# Pi-Fan-Controller_2021-02-07-eda-export.net
KiCad netlist of a schematic drawn in EasyEDA
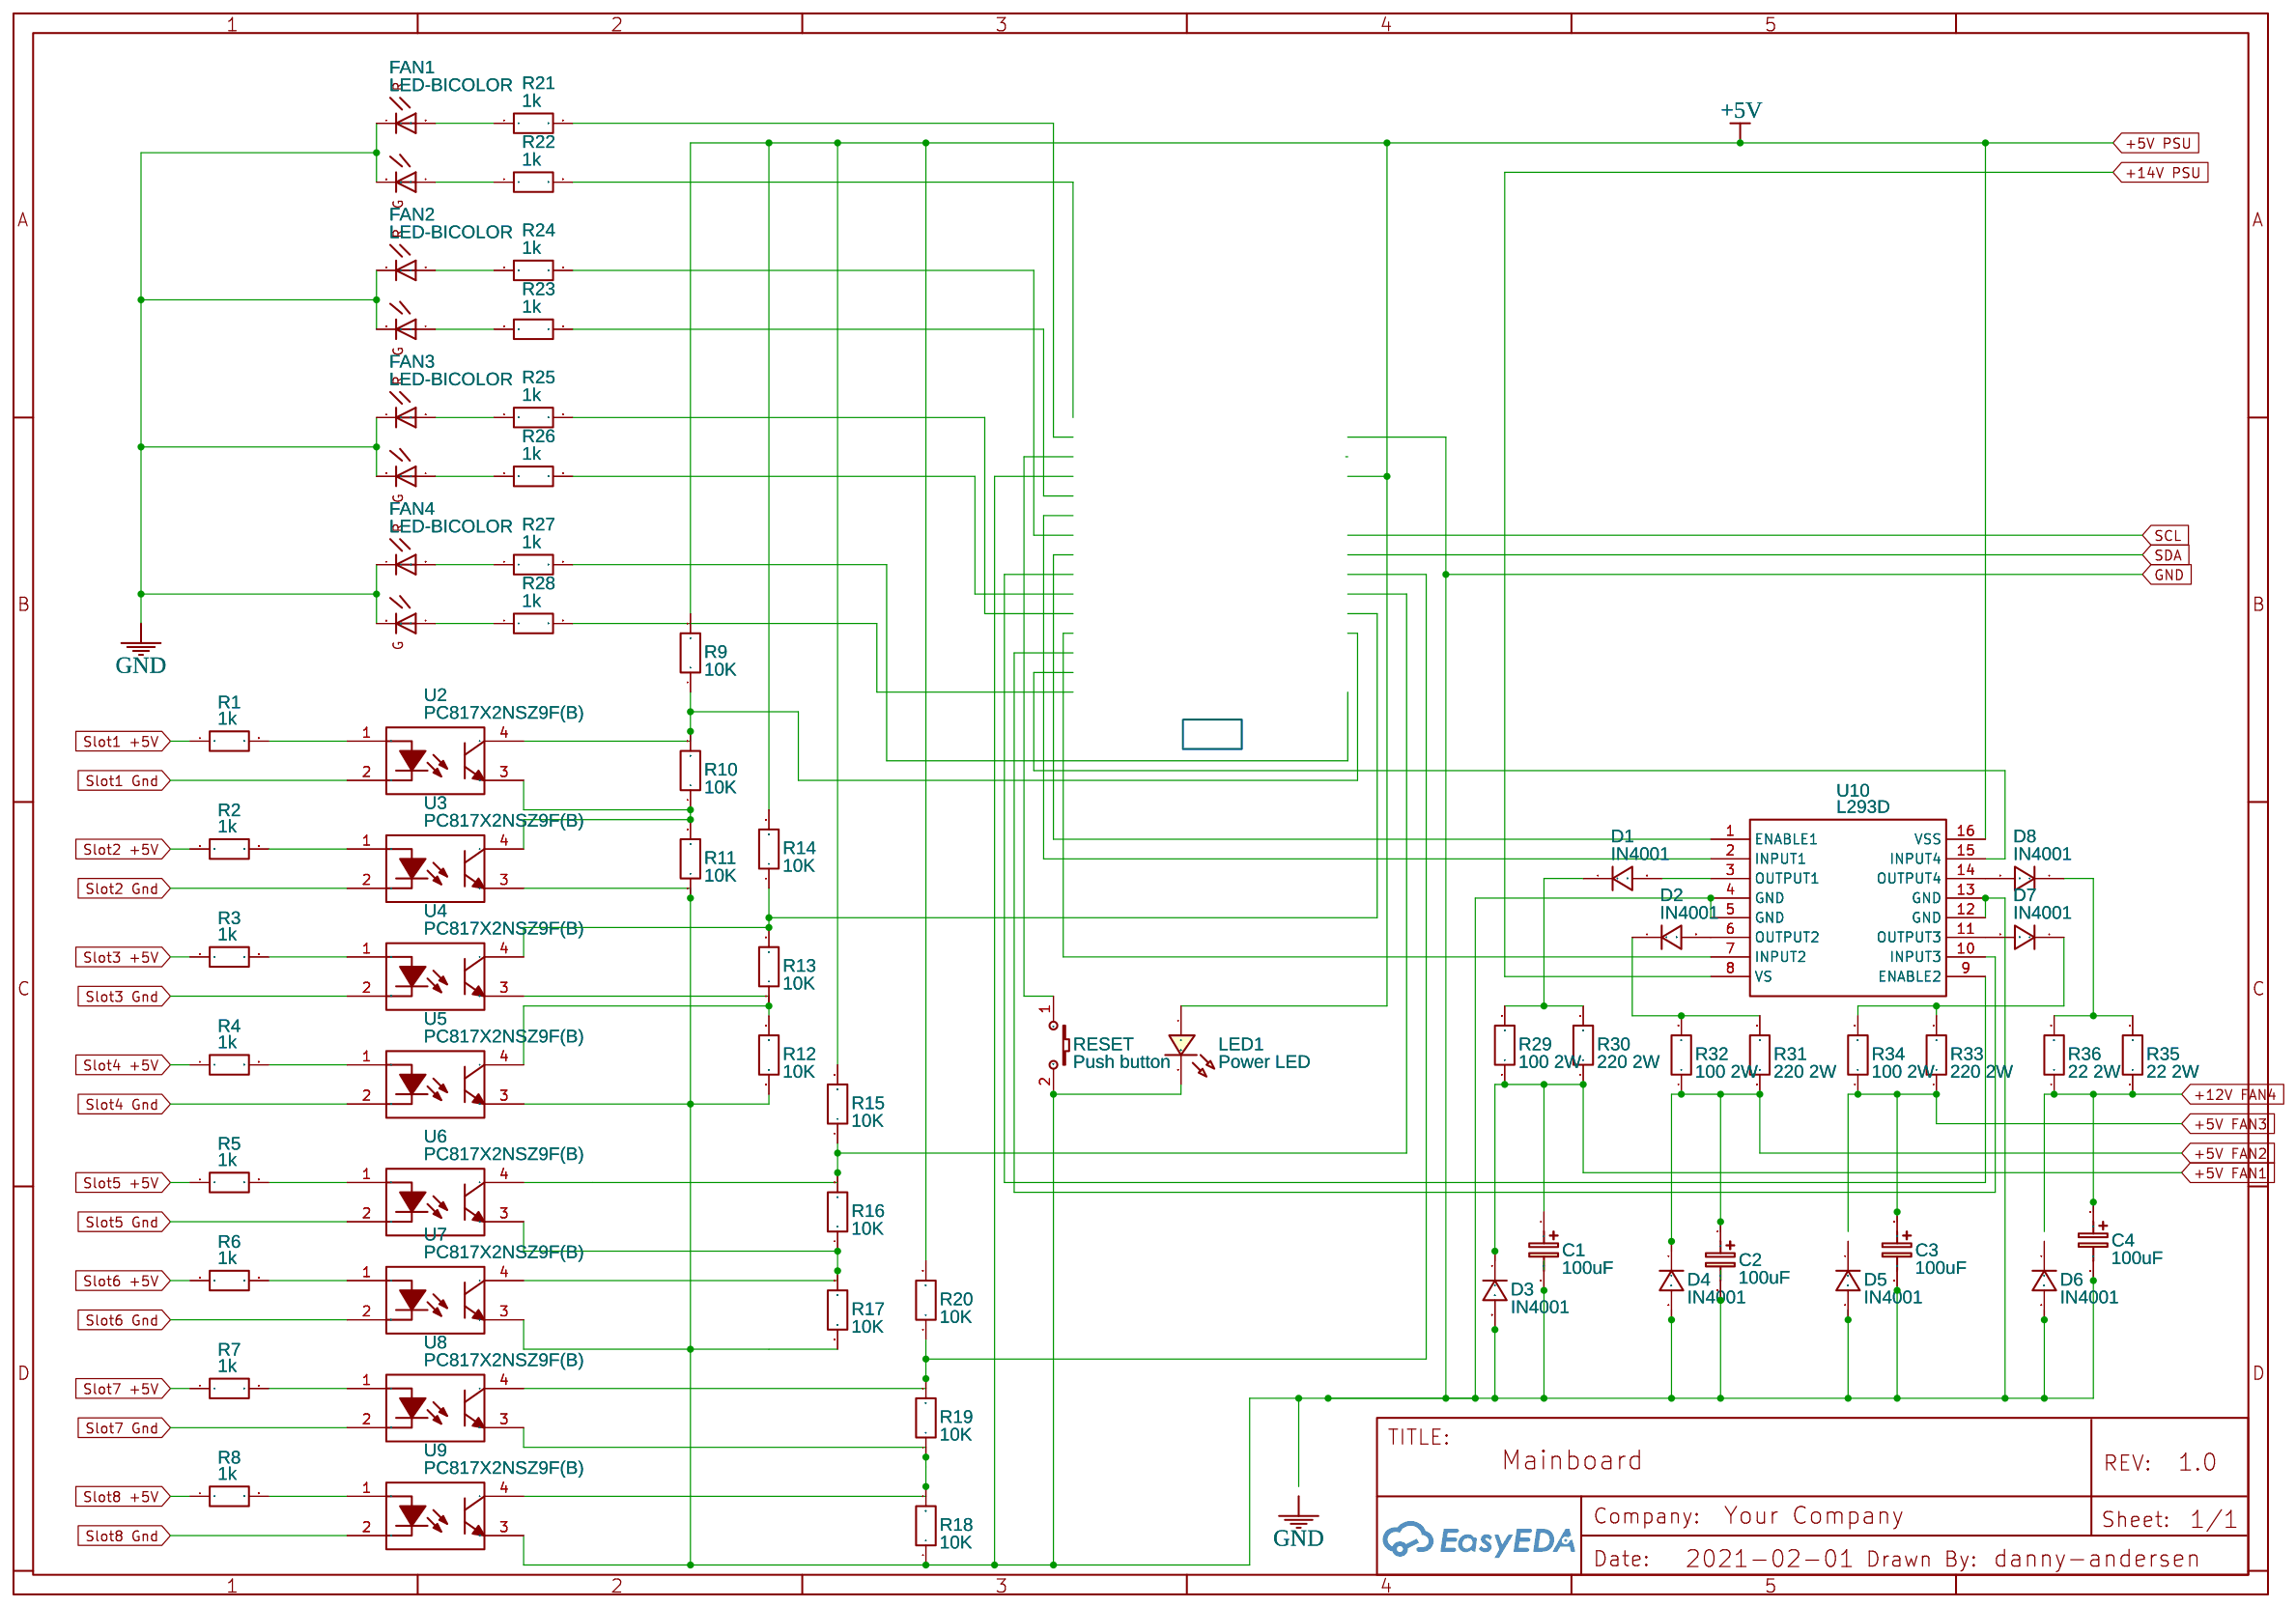
[diagram p0: schematic sheet]

(export (version "E")
  (design (tool "Eeschema 10.0.6"))
  (components
    (comp (ref "C1") (value "100uF") (libsource (lib "") (part "C_Tan_SMD_A_EU")))
    (comp (ref "C2") (value "100uF") (libsource (lib "") (part "C_Tan_SMD_A_EU")))
    (comp (ref "C3") (value "100uF") (libsource (lib "") (part "C_Tan_SMD_A_EU")))
    (comp (ref "C4") (value "100uF") (libsource (lib "") (part "C_Tan_SMD_A_EU_1")))
    (comp (ref "D1") (value "IN4001") (libsource (lib "") (part "IN4001_1")))
    (comp (ref "D2") (value "IN4001") (libsource (lib "") (part "IN4001_1")))
    (comp (ref "D3") (value "IN4001") (libsource (lib "") (part "IN4001")))
    (comp (ref "D4") (value "IN4001") (libsource (lib "") (part "IN4001")))
    (comp (ref "D5") (value "IN4001") (libsource (lib "") (part "IN4001")))
    (comp (ref "D6") (value "IN4001") (libsource (lib "") (part "IN4001")))
    (comp (ref "D7") (value "IN4001") (libsource (lib "") (part "IN4001_2")))
    (comp (ref "D8") (value "IN4001") (libsource (lib "") (part "IN4001_2")))
    (comp (ref "FAN1")
      (value "LED-BICOLOR")
      (fields (field (name "BOM_Manufacturer Part") "?"))
      (libsource (lib "") (part "Unknown_205_-750"))
    )
    (comp (ref "FAN2")
      (value "LED-BICOLOR")
      (fields (field (name "BOM_Manufacturer Part") "?"))
      (libsource (lib "") (part "Unknown_205_-675"))
    )
    (comp (ref "FAN3")
      (value "LED-BICOLOR")
      (fields (field (name "BOM_Manufacturer Part") "?"))
      (libsource (lib "") (part "Unknown_205_-600"))
    )
    (comp (ref "FAN4")
      (value "LED-BICOLOR")
      (fields (field (name "BOM_Manufacturer Part") "?"))
      (libsource (lib "") (part "Unknown_205_-525"))
    )
    (comp (ref "LED1")
      (value "Power LED")
      (fields
        (field (name "BOM_Manufacturer Part") "19-217/R6C-AL1M2VY/3T")
        (field (name "BOM_Supplier Part") "C72044")
      )
      (libsource (lib "") (part "LED-0603_R"))
    )
    (comp (ref "R1") (value "1k") (libsource (lib "") (part "R_0603_EU_1")))
    (comp (ref "R2") (value "1k") (libsource (lib "") (part "R_0603_EU_1")))
    (comp (ref "R3") (value "1k") (libsource (lib "") (part "R_0603_EU_1")))
    (comp (ref "R4") (value "1k") (libsource (lib "") (part "R_0603_EU_1")))
    (comp (ref "R5") (value "1k") (libsource (lib "") (part "R_0603_EU_1")))
    (comp (ref "R6") (value "1k") (libsource (lib "") (part "R_0603_EU_1")))
    (comp (ref "R7") (value "1k") (libsource (lib "") (part "R_0603_EU_1")))
    (comp (ref "R8") (value "1k") (libsource (lib "") (part "R_0603_EU_1")))
    (comp (ref "R9") (value "10K") (libsource (lib "") (part "R_0603_EU")))
    (comp (ref "R10") (value "10K") (libsource (lib "") (part "R_0603_EU")))
    (comp (ref "R11") (value "10K") (libsource (lib "") (part "R_0603_EU")))
    (comp (ref "R12") (value "10K") (libsource (lib "") (part "R_0603_EU")))
    (comp (ref "R13") (value "10K") (libsource (lib "") (part "R_0603_EU")))
    (comp (ref "R14") (value "10K") (libsource (lib "") (part "R_0603_EU")))
    (comp (ref "R15") (value "10K") (libsource (lib "") (part "R_0603_EU")))
    (comp (ref "R16") (value "10K") (libsource (lib "") (part "R_0603_EU")))
    (comp (ref "R17") (value "10K") (libsource (lib "") (part "R_0603_EU")))
    (comp (ref "R18") (value "10K") (libsource (lib "") (part "R_0603_EU")))
    (comp (ref "R19") (value "10K") (libsource (lib "") (part "R_0603_EU")))
    (comp (ref "R20") (value "10K") (libsource (lib "") (part "R_0603_EU")))
    (comp (ref "R21") (value "1k") (libsource (lib "") (part "R_0603_EU_1")))
    (comp (ref "R22") (value "1k") (libsource (lib "") (part "R_0603_EU_1")))
    (comp (ref "R23") (value "1k") (libsource (lib "") (part "R_0603_EU_1")))
    (comp (ref "R24") (value "1k") (libsource (lib "") (part "R_0603_EU_1")))
    (comp (ref "R25") (value "1k") (libsource (lib "") (part "R_0603_EU_1")))
    (comp (ref "R26") (value "1k") (libsource (lib "") (part "R_0603_EU_1")))
    (comp (ref "R27") (value "1k") (libsource (lib "") (part "R_0603_EU_1")))
    (comp (ref "R28") (value "1k") (libsource (lib "") (part "R_0603_EU_1")))
    (comp (ref "R29") (value "100 2W") (libsource (lib "") (part "R_0603_EU")))
    (comp (ref "R30") (value "220 2W") (libsource (lib "") (part "R_0603_EU")))
    (comp (ref "R31") (value "220 2W") (libsource (lib "") (part "R_0603_EU")))
    (comp (ref "R32") (value "100 2W") (libsource (lib "") (part "R_0603_EU")))
    (comp (ref "R33") (value "220 2W") (libsource (lib "") (part "R_0603_EU")))
    (comp (ref "R34") (value "100 2W") (libsource (lib "") (part "R_0603_EU")))
    (comp (ref "R35") (value "22 2W") (libsource (lib "") (part "R_0603_EU")))
    (comp (ref "R36") (value "22 2W") (libsource (lib "") (part "R_0603_EU")))
    (comp (ref "RESET")
      (value "Push button")
      (fields
        (field (name "BOM_Manufacturer Part") "K2-1107ST-A4SW-06")
        (field (name "BOM_Supplier Part") "C118141")
      )
      (libsource (lib "") (part "K2-3.6×6.1_SMD"))
    )
    (comp (ref "U2")
      (value "PC817X2NSZ9F(B)")
      (fields (field (name "BOM_Supplier Part") "C60965"))
      (libsource (lib "") (part "PC817X2NSZ9F(B)"))
    )
    (comp (ref "U3")
      (value "PC817X2NSZ9F(B)")
      (fields (field (name "BOM_Supplier Part") "C60965"))
      (libsource (lib "") (part "PC817X2NSZ9F(B)"))
    )
    (comp (ref "U4")
      (value "PC817X2NSZ9F(B)")
      (fields (field (name "BOM_Supplier Part") "C60965"))
      (libsource (lib "") (part "PC817X2NSZ9F(B)"))
    )
    (comp (ref "U5")
      (value "PC817X2NSZ9F(B)")
      (fields (field (name "BOM_Supplier Part") "C60965"))
      (libsource (lib "") (part "PC817X2NSZ9F(B)"))
    )
    (comp (ref "U6")
      (value "PC817X2NSZ9F(B)")
      (fields (field (name "BOM_Supplier Part") "C60965"))
      (libsource (lib "") (part "PC817X2NSZ9F(B)"))
    )
    (comp (ref "U7")
      (value "PC817X2NSZ9F(B)")
      (fields (field (name "BOM_Supplier Part") "C60965"))
      (libsource (lib "") (part "PC817X2NSZ9F(B)"))
    )
    (comp (ref "U8")
      (value "PC817X2NSZ9F(B)")
      (fields (field (name "BOM_Supplier Part") "C60965"))
      (libsource (lib "") (part "PC817X2NSZ9F(B)"))
    )
    (comp (ref "U9")
      (value "PC817X2NSZ9F(B)")
      (fields (field (name "BOM_Supplier Part") "C60965"))
      (libsource (lib "") (part "PC817X2NSZ9F(B)"))
    )
    (comp (ref "U10")
      (value "L293D")
      (fields (field (name "BOM_Supplier Part") "C12340"))
      (libsource (lib "") (part "L293D"))
    )
  )
  (nets
    (net (code "1") (name "+5V FAN1") (class "Default")
      (node (ref "C1") (pin "1") (pinfunction "1_1") (pintype "unspecified"))
      (node (ref "D3") (pin "1") (pinfunction "1_1") (pintype "unspecified"))
      (node (ref "R29") (pin "1") (pinfunction "1_1") (pintype "unspecified"))
      (node (ref "R30") (pin "1") (pinfunction "1_1") (pintype "unspecified"))
    )
    (net (code "2") (name "+5V FAN2") (class "Default")
      (node (ref "C2") (pin "1") (pinfunction "1_1") (pintype "unspecified"))
      (node (ref "D4") (pin "1") (pinfunction "1_1") (pintype "unspecified"))
      (node (ref "R31") (pin "1") (pinfunction "1_1") (pintype "unspecified"))
      (node (ref "R32") (pin "1") (pinfunction "1_1") (pintype "unspecified"))
    )
    (net (code "3") (name "+5V FAN3") (class "Default")
      (node (ref "C3") (pin "1") (pinfunction "1_1") (pintype "unspecified"))
      (node (ref "R33") (pin "1") (pinfunction "1_1") (pintype "unspecified"))
      (node (ref "R34") (pin "1") (pinfunction "1_1") (pintype "unspecified"))
    )
    (net (code "4") (name "+5V PSU") (class "Default")
      (node (ref "LED1") (pin "1") (pinfunction "1_1") (pintype "unspecified"))
      (node (ref "R14") (pin "2") (pinfunction "2_2") (pintype "unspecified"))
      (node (ref "R15") (pin "2") (pinfunction "2_2") (pintype "unspecified"))
      (node (ref "R20") (pin "2") (pinfunction "2_2") (pintype "unspecified"))
      (node (ref "R9") (pin "2") (pinfunction "2_2") (pintype "unspecified"))
      (node (ref "U10") (pin "16") (pinfunction "VSS_16") (pintype "unspecified"))
    )
    (net (code "5") (name "+12V FAN4") (class "Default")
      (node (ref "C4") (pin "1") (pinfunction "1_1") (pintype "unspecified"))
      (node (ref "R35") (pin "1") (pinfunction "1_1") (pintype "unspecified"))
      (node (ref "R36") (pin "1") (pinfunction "1_1") (pintype "unspecified"))
    )
    (net (code "6") (name "+14V PSU") (class "Default")
      (node (ref "U10") (pin "8") (pinfunction "VS_8") (pintype "unspecified"))
    )
    (net (code "7") (name "GND") (class "Default")
      (node (ref "C1") (pin "2") (pinfunction "2_2") (pintype "unspecified"))
      (node (ref "C2") (pin "2") (pinfunction "2_2") (pintype "unspecified"))
      (node (ref "C3") (pin "2") (pinfunction "2_2") (pintype "unspecified"))
      (node (ref "C4") (pin "2") (pinfunction "2_2") (pintype "unspecified"))
      (node (ref "D3") (pin "2") (pinfunction "2_2") (pintype "unspecified"))
      (node (ref "D4") (pin "2") (pinfunction "2_2") (pintype "unspecified"))
      (node (ref "D5") (pin "2") (pinfunction "2_2") (pintype "unspecified"))
      (node (ref "D6") (pin "2") (pinfunction "2_2") (pintype "unspecified"))
      (node (ref "FAN1") (pin "3") (pinfunction "3_3") (pintype "unspecified"))
      (node (ref "FAN1") (pin "4") (pinfunction "4_4") (pintype "unspecified"))
      (node (ref "FAN2") (pin "3") (pinfunction "3_3") (pintype "unspecified"))
      (node (ref "FAN2") (pin "4") (pinfunction "4_4") (pintype "unspecified"))
      (node (ref "FAN3") (pin "3") (pinfunction "3_3") (pintype "unspecified"))
      (node (ref "FAN3") (pin "4") (pinfunction "4_4") (pintype "unspecified"))
      (node (ref "FAN4") (pin "3") (pinfunction "3_3") (pintype "unspecified"))
      (node (ref "FAN4") (pin "4") (pinfunction "4_4") (pintype "unspecified"))
      (node (ref "LED1") (pin "2") (pinfunction "2_2") (pintype "unspecified"))
      (node (ref "R11") (pin "1") (pinfunction "1_1") (pintype "unspecified"))
      (node (ref "R12") (pin "1") (pinfunction "1_1") (pintype "unspecified"))
      (node (ref "R17") (pin "1") (pinfunction "1_1") (pintype "unspecified"))
      (node (ref "R18") (pin "1") (pinfunction "1_1") (pintype "unspecified"))
      (node (ref "RESET") (pin "2") (pinfunction "2_2") (pintype "unspecified"))
      (node (ref "U10") (pin "12") (pinfunction "GND_12") (pintype "unspecified"))
      (node (ref "U10") (pin "13") (pinfunction "GND_13") (pintype "unspecified"))
      (node (ref "U10") (pin "4") (pinfunction "GND_4") (pintype "unspecified"))
      (node (ref "U10") (pin "5") (pinfunction "GND_5") (pintype "unspecified"))
      (node (ref "U3") (pin "3") (pinfunction "3_3") (pintype "unspecified"))
      (node (ref "U5") (pin "3") (pinfunction "3_3") (pintype "unspecified"))
      (node (ref "U7") (pin "3") (pinfunction "3_3") (pintype "unspecified"))
      (node (ref "U9") (pin "3") (pinfunction "3_3") (pintype "unspecified"))
    )
    (net (code "8") (name "Net-(D1-Pad1)") (class "Default")
      (node (ref "D1") (pin "1") (pinfunction "1_1") (pintype "unspecified"))
      (node (ref "R29") (pin "2") (pinfunction "2_2") (pintype "unspecified"))
      (node (ref "R30") (pin "2") (pinfunction "2_2") (pintype "unspecified"))
    )
    (net (code "9") (name "Net-(D2-Pad1)") (class "Default")
      (node (ref "D2") (pin "1") (pinfunction "1_1") (pintype "unspecified"))
      (node (ref "R31") (pin "2") (pinfunction "2_2") (pintype "unspecified"))
      (node (ref "R32") (pin "2") (pinfunction "2_2") (pintype "unspecified"))
    )
    (net (code "10") (name "Net-(D7-Pad1)") (class "Default")
      (node (ref "D7") (pin "1") (pinfunction "1_1") (pintype "unspecified"))
      (node (ref "R33") (pin "2") (pinfunction "2_2") (pintype "unspecified"))
      (node (ref "R34") (pin "2") (pinfunction "2_2") (pintype "unspecified"))
    )
    (net (code "11") (name "Net-(D8-Pad1)") (class "Default")
      (node (ref "D8") (pin "1") (pinfunction "1_1") (pintype "unspecified"))
      (node (ref "R35") (pin "2") (pinfunction "2_2") (pintype "unspecified"))
      (node (ref "R36") (pin "2") (pinfunction "2_2") (pintype "unspecified"))
    )
    (net (code "12") (name "Net-(FAN1-Pad1)") (class "Default")
      (node (ref "FAN1") (pin "1") (pinfunction "1_1") (pintype "unspecified"))
      (node (ref "R22") (pin "1") (pinfunction "1_1") (pintype "unspecified"))
    )
    (net (code "13") (name "Net-(FAN1-Pad2)") (class "Default")
      (node (ref "FAN1") (pin "2") (pinfunction "2_2") (pintype "unspecified"))
      (node (ref "R21") (pin "1") (pinfunction "1_1") (pintype "unspecified"))
    )
    (net (code "14") (name "Net-(FAN2-Pad1)") (class "Default")
      (node (ref "FAN2") (pin "1") (pinfunction "1_1") (pintype "unspecified"))
      (node (ref "R23") (pin "1") (pinfunction "1_1") (pintype "unspecified"))
    )
    (net (code "15") (name "Net-(FAN2-Pad2)") (class "Default")
      (node (ref "FAN2") (pin "2") (pinfunction "2_2") (pintype "unspecified"))
      (node (ref "R24") (pin "1") (pinfunction "1_1") (pintype "unspecified"))
    )
    (net (code "16") (name "Net-(FAN3-Pad1)") (class "Default")
      (node (ref "FAN3") (pin "1") (pinfunction "1_1") (pintype "unspecified"))
      (node (ref "R26") (pin "1") (pinfunction "1_1") (pintype "unspecified"))
    )
    (net (code "17") (name "Net-(FAN3-Pad2)") (class "Default")
      (node (ref "FAN3") (pin "2") (pinfunction "2_2") (pintype "unspecified"))
      (node (ref "R25") (pin "1") (pinfunction "1_1") (pintype "unspecified"))
    )
    (net (code "18") (name "Net-(FAN4-Pad1)") (class "Default")
      (node (ref "FAN4") (pin "1") (pinfunction "1_1") (pintype "unspecified"))
      (node (ref "R28") (pin "1") (pinfunction "1_1") (pintype "unspecified"))
    )
    (net (code "19") (name "Net-(FAN4-Pad2)") (class "Default")
      (node (ref "FAN4") (pin "2") (pinfunction "2_2") (pintype "unspecified"))
      (node (ref "R27") (pin "1") (pinfunction "1_1") (pintype "unspecified"))
    )
    (net (code "20") (name "Net-(R1-Pad2)") (class "Default")
      (node (ref "R1") (pin "2") (pinfunction "2_2") (pintype "unspecified"))
      (node (ref "U2") (pin "1") (pinfunction "1_1") (pintype "unspecified"))
    )
    (net (code "21") (name "Net-(R2-Pad2)") (class "Default")
      (node (ref "R2") (pin "2") (pinfunction "2_2") (pintype "unspecified"))
      (node (ref "U3") (pin "1") (pinfunction "1_1") (pintype "unspecified"))
    )
    (net (code "22") (name "Net-(R3-Pad2)") (class "Default")
      (node (ref "R3") (pin "2") (pinfunction "2_2") (pintype "unspecified"))
      (node (ref "U4") (pin "1") (pinfunction "1_1") (pintype "unspecified"))
    )
    (net (code "23") (name "Net-(R4-Pad2)") (class "Default")
      (node (ref "R4") (pin "2") (pinfunction "2_2") (pintype "unspecified"))
      (node (ref "U5") (pin "1") (pinfunction "1_1") (pintype "unspecified"))
    )
    (net (code "24") (name "Net-(R5-Pad2)") (class "Default")
      (node (ref "R5") (pin "2") (pinfunction "2_2") (pintype "unspecified"))
      (node (ref "U6") (pin "1") (pinfunction "1_1") (pintype "unspecified"))
    )
    (net (code "25") (name "Net-(R6-Pad2)") (class "Default")
      (node (ref "R6") (pin "2") (pinfunction "2_2") (pintype "unspecified"))
      (node (ref "U7") (pin "1") (pinfunction "1_1") (pintype "unspecified"))
    )
    (net (code "26") (name "Net-(R7-Pad2)") (class "Default")
      (node (ref "R7") (pin "2") (pinfunction "2_2") (pintype "unspecified"))
      (node (ref "U8") (pin "1") (pinfunction "1_1") (pintype "unspecified"))
    )
    (net (code "27") (name "Net-(R8-Pad2)") (class "Default")
      (node (ref "R8") (pin "2") (pinfunction "2_2") (pintype "unspecified"))
      (node (ref "U9") (pin "1") (pinfunction "1_1") (pintype "unspecified"))
    )
    (net (code "28") (name "Net-(R10-Pad1)") (class "Default")
      (node (ref "R10") (pin "1") (pinfunction "1_1") (pintype "unspecified"))
      (node (ref "R11") (pin "2") (pinfunction "2_2") (pintype "unspecified"))
      (node (ref "U2") (pin "3") (pinfunction "3_3") (pintype "unspecified"))
      (node (ref "U3") (pin "4") (pinfunction "4_4") (pintype "unspecified"))
    )
    (net (code "29") (name "Net-(R10-Pad2)") (class "Default")
      (node (ref "R10") (pin "2") (pinfunction "2_2") (pintype "unspecified"))
      (node (ref "R9") (pin "1") (pinfunction "1_1") (pintype "unspecified"))
      (node (ref "U2") (pin "4") (pinfunction "4_4") (pintype "unspecified"))
    )
    (net (code "30") (name "Net-(R12-Pad2)") (class "Default")
      (node (ref "R12") (pin "2") (pinfunction "2_2") (pintype "unspecified"))
      (node (ref "R13") (pin "1") (pinfunction "1_1") (pintype "unspecified"))
      (node (ref "U4") (pin "3") (pinfunction "3_3") (pintype "unspecified"))
      (node (ref "U5") (pin "4") (pinfunction "4_4") (pintype "unspecified"))
    )
    (net (code "31") (name "Net-(R13-Pad2)") (class "Default")
      (node (ref "R13") (pin "2") (pinfunction "2_2") (pintype "unspecified"))
      (node (ref "R14") (pin "1") (pinfunction "1_1") (pintype "unspecified"))
      (node (ref "U4") (pin "4") (pinfunction "4_4") (pintype "unspecified"))
    )
    (net (code "32") (name "Net-(R15-Pad1)") (class "Default")
      (node (ref "R15") (pin "1") (pinfunction "1_1") (pintype "unspecified"))
      (node (ref "R16") (pin "2") (pinfunction "2_2") (pintype "unspecified"))
      (node (ref "U6") (pin "4") (pinfunction "4_4") (pintype "unspecified"))
    )
    (net (code "33") (name "Net-(R16-Pad1)") (class "Default")
      (node (ref "R16") (pin "1") (pinfunction "1_1") (pintype "unspecified"))
      (node (ref "R17") (pin "2") (pinfunction "2_2") (pintype "unspecified"))
      (node (ref "U6") (pin "3") (pinfunction "3_3") (pintype "unspecified"))
      (node (ref "U7") (pin "4") (pinfunction "4_4") (pintype "unspecified"))
    )
    (net (code "34") (name "Net-(R18-Pad2)") (class "Default")
      (node (ref "R18") (pin "2") (pinfunction "2_2") (pintype "unspecified"))
      (node (ref "R19") (pin "1") (pinfunction "1_1") (pintype "unspecified"))
      (node (ref "U8") (pin "3") (pinfunction "3_3") (pintype "unspecified"))
      (node (ref "U9") (pin "4") (pinfunction "4_4") (pintype "unspecified"))
    )
    (net (code "35") (name "Net-(R19-Pad2)") (class "Default")
      (node (ref "R19") (pin "2") (pinfunction "2_2") (pintype "unspecified"))
      (node (ref "R20") (pin "1") (pinfunction "1_1") (pintype "unspecified"))
      (node (ref "U8") (pin "4") (pinfunction "4_4") (pintype "unspecified"))
    )
    (net (code "36") (name "Net-(U10-OUTPUT1)") (class "Default")
      (node (ref "D1") (pin "2") (pinfunction "2_2") (pintype "unspecified"))
      (node (ref "U10") (pin "3") (pinfunction "OUTPUT1_3") (pintype "unspecified"))
    )
    (net (code "37") (name "Net-(U10-OUTPUT2)") (class "Default")
      (node (ref "D2") (pin "2") (pinfunction "2_2") (pintype "unspecified"))
      (node (ref "U10") (pin "6") (pinfunction "OUTPUT2_6") (pintype "unspecified"))
    )
    (net (code "38") (name "Net-(U10-OUTPUT3)") (class "Default")
      (node (ref "D7") (pin "2") (pinfunction "2_2") (pintype "unspecified"))
      (node (ref "U10") (pin "11") (pinfunction "OUTPUT3_11") (pintype "unspecified"))
    )
    (net (code "39") (name "Net-(U10-OUTPUT4)") (class "Default")
      (node (ref "D8") (pin "2") (pinfunction "2_2") (pintype "unspecified"))
      (node (ref "U10") (pin "14") (pinfunction "OUTPUT4_14") (pintype "unspecified"))
    )
    (net (code "42") (name "Slot1 +5V") (class "Default")
      (node (ref "R1") (pin "1") (pinfunction "1_1") (pintype "unspecified"))
    )
    (net (code "43") (name "Slot1 Gnd") (class "Default")
      (node (ref "U2") (pin "2") (pinfunction "2_2") (pintype "unspecified"))
    )
    (net (code "44") (name "Slot2 +5V") (class "Default")
      (node (ref "R2") (pin "1") (pinfunction "1_1") (pintype "unspecified"))
    )
    (net (code "45") (name "Slot2 Gnd") (class "Default")
      (node (ref "U3") (pin "2") (pinfunction "2_2") (pintype "unspecified"))
    )
    (net (code "46") (name "Slot3 +5V") (class "Default")
      (node (ref "R3") (pin "1") (pinfunction "1_1") (pintype "unspecified"))
    )
    (net (code "47") (name "Slot3 Gnd") (class "Default")
      (node (ref "U4") (pin "2") (pinfunction "2_2") (pintype "unspecified"))
    )
    (net (code "48") (name "Slot4 +5V") (class "Default")
      (node (ref "R4") (pin "1") (pinfunction "1_1") (pintype "unspecified"))
    )
    (net (code "49") (name "Slot4 Gnd") (class "Default")
      (node (ref "U5") (pin "2") (pinfunction "2_2") (pintype "unspecified"))
    )
    (net (code "50") (name "Slot5 +5V") (class "Default")
      (node (ref "R5") (pin "1") (pinfunction "1_1") (pintype "unspecified"))
    )
    (net (code "51") (name "Slot5 Gnd") (class "Default")
      (node (ref "U6") (pin "2") (pinfunction "2_2") (pintype "unspecified"))
    )
    (net (code "52") (name "Slot6 +5V") (class "Default")
      (node (ref "R6") (pin "1") (pinfunction "1_1") (pintype "unspecified"))
    )
    (net (code "53") (name "Slot6 Gnd") (class "Default")
      (node (ref "U7") (pin "2") (pinfunction "2_2") (pintype "unspecified"))
    )
    (net (code "54") (name "Slot7 +5V") (class "Default")
      (node (ref "R7") (pin "1") (pinfunction "1_1") (pintype "unspecified"))
    )
    (net (code "55") (name "Slot7 Gnd") (class "Default")
      (node (ref "U8") (pin "2") (pinfunction "2_2") (pintype "unspecified"))
    )
    (net (code "56") (name "Slot8 +5V") (class "Default")
      (node (ref "R8") (pin "1") (pinfunction "1_1") (pintype "unspecified"))
    )
    (net (code "57") (name "Slot8 Gnd") (class "Default")
      (node (ref "U9") (pin "2") (pinfunction "2_2") (pintype "unspecified"))
    )
    (net (code "58") (name "unconnected-(D5-Pad1)") (class "Default")
      (node (ref "D5") (pin "1") (pinfunction "1_1") (pintype "unspecified"))
    )
    (net (code "59") (name "unconnected-(D6-Pad1)") (class "Default")
      (node (ref "D6") (pin "1") (pinfunction "1_1") (pintype "unspecified"))
    )
    (net (code "60") (name "unconnected-(R21-Pad2)") (class "Default")
      (node (ref "R21") (pin "2") (pinfunction "2_2") (pintype "unspecified"))
    )
    (net (code "61") (name "unconnected-(R22-Pad2)") (class "Default")
      (node (ref "R22") (pin "2") (pinfunction "2_2") (pintype "unspecified"))
    )
    (net (code "62") (name "unconnected-(R23-Pad2)") (class "Default")
      (node (ref "R23") (pin "2") (pinfunction "2_2") (pintype "unspecified"))
    )
    (net (code "63") (name "unconnected-(R24-Pad2)") (class "Default")
      (node (ref "R24") (pin "2") (pinfunction "2_2") (pintype "unspecified"))
    )
    (net (code "64") (name "unconnected-(R25-Pad2)") (class "Default")
      (node (ref "R25") (pin "2") (pinfunction "2_2") (pintype "unspecified"))
    )
    (net (code "65") (name "unconnected-(R26-Pad2)") (class "Default")
      (node (ref "R26") (pin "2") (pinfunction "2_2") (pintype "unspecified"))
    )
    (net (code "66") (name "unconnected-(R27-Pad2)") (class "Default")
      (node (ref "R27") (pin "2") (pinfunction "2_2") (pintype "unspecified"))
    )
    (net (code "67") (name "unconnected-(R28-Pad2)") (class "Default")
      (node (ref "R28") (pin "2") (pinfunction "2_2") (pintype "unspecified"))
    )
    (net (code "68") (name "unconnected-(RESET-Pad1)") (class "Default")
      (node (ref "RESET") (pin "1") (pinfunction "1_1") (pintype "unspecified"))
    )
    (net (code "69") (name "unconnected-(U10-ENABLE1-Pad1)") (class "Default")
      (node (ref "U10") (pin "1") (pinfunction "ENABLE1_1") (pintype "unspecified"))
    )
    (net (code "70") (name "unconnected-(U10-ENABLE2-Pad9)") (class "Default")
      (node (ref "U10") (pin "9") (pinfunction "ENABLE2_9") (pintype "unspecified"))
    )
    (net (code "71") (name "unconnected-(U10-INPUT1-Pad2)") (class "Default")
      (node (ref "U10") (pin "2") (pinfunction "INPUT1_2") (pintype "unspecified"))
    )
    (net (code "72") (name "unconnected-(U10-INPUT2-Pad7)") (class "Default")
      (node (ref "U10") (pin "7") (pinfunction "INPUT2_7") (pintype "unspecified"))
    )
    (net (code "73") (name "unconnected-(U10-INPUT3-Pad10)") (class "Default")
      (node (ref "U10") (pin "10") (pinfunction "INPUT3_10") (pintype "unspecified"))
    )
    (net (code "74") (name "unconnected-(U10-INPUT4-Pad15)") (class "Default")
      (node (ref "U10") (pin "15") (pinfunction "INPUT4_15") (pintype "unspecified"))
    )
  )
)
